# novelkey_esp.net
KiCad netlist of a schematic drawn in EAGLE
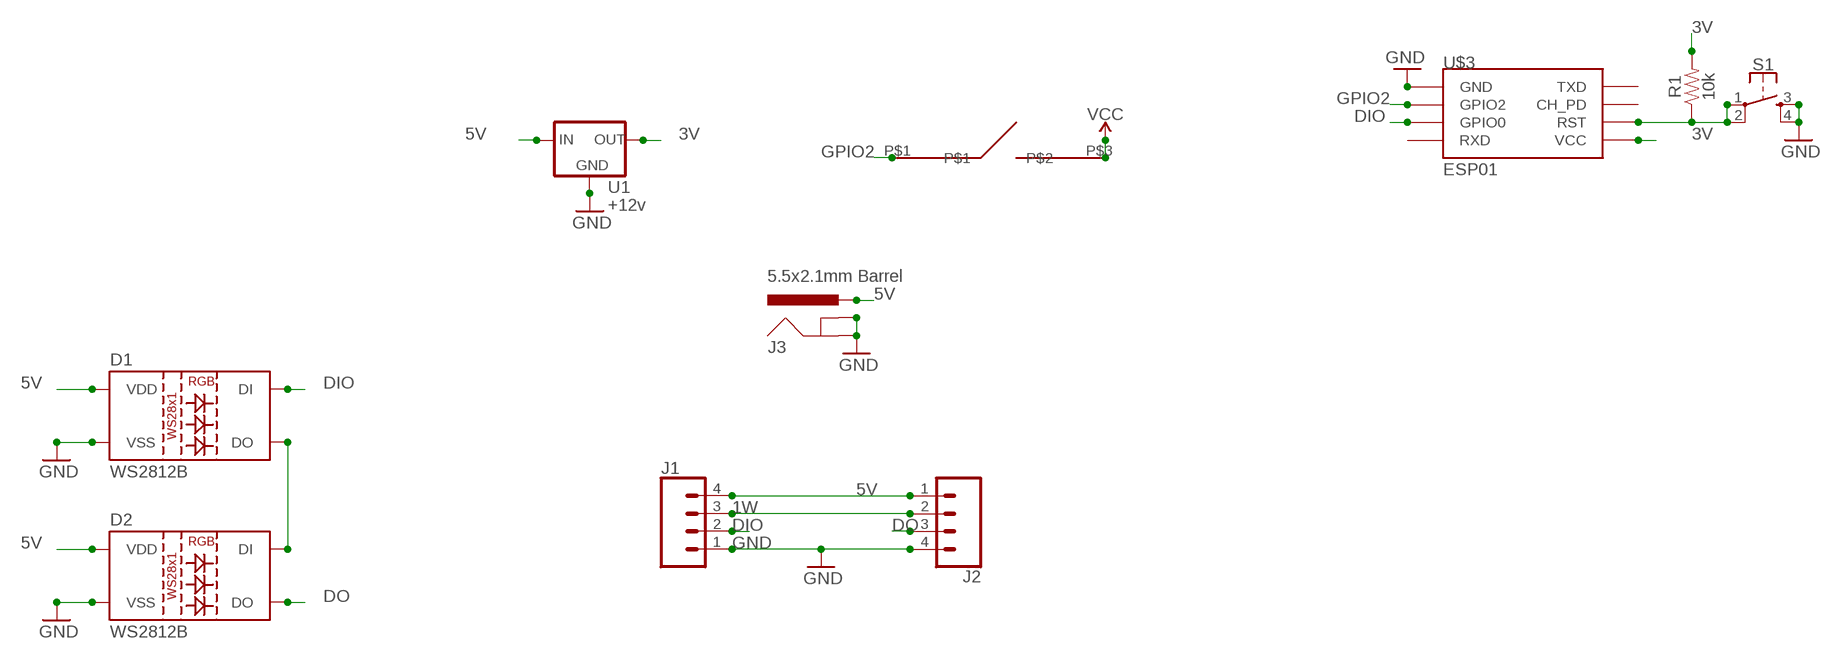
[diagram p0: schematic, sheet 1]

(export (version "E")
  (design (tool "Eeschema 10.0.6"))
  (components
    (comp (ref "D1")
      (value "WS2812B")
      (footprint "eagle-import:WS2812B")
      (libsource (lib "eagle-import") (part "WS2812B"))
    )
    (comp (ref "D2")
      (value "WS2812B")
      (footprint "eagle-import:WS2812B")
      (libsource (lib "eagle-import") (part "WS2812B"))
    )
    (comp (ref "J1")
      (value "CONN_04SMD2")
      (footprint "eagle-import:1X04_1MM_RA")
      (libsource (lib "eagle-import") (part "CONN_04SMD2"))
    )
    (comp (ref "J2")
      (value "CONN_04SMD2")
      (footprint "eagle-import:1X04_1MM_RA")
      (libsource (lib "eagle-import") (part "CONN_04SMD2"))
    )
    (comp (ref "J3")
      (value "5.5x2.1mm Barrel")
      (footprint "eagle-import:POWER_JACK_SMD")
      (libsource (lib "eagle-import") (part "POWER_JACKSMD"))
    )
    (comp (ref "R1")
      (value "10k")
      (footprint "eagle-import:0603")
      (libsource (lib "eagle-import") (part "10KOHM-0603-1/10W-1%"))
    )
    (comp (ref "S1")
      (value "MOMENTARY-SWITCH-SPST-2-SMD-4.6X2.8MM")
      (footprint "eagle-import:TACTILE_SWITCH_SMD_4.6X2.8MM")
      (libsource (lib "eagle-import") (part "MOMENTARY-SWITCH-SPST-2-SMD-4.6X2.8MM"))
    )
    (comp (ref "U$1")
      (value "NOVELKEY")
      (footprint "eagle-import:NOVELKEY")
      (libsource (lib "eagle-import") (part "NOVELKEY"))
    )
    (comp (ref "U$3")
      (value "ESP01")
      (footprint "eagle-import:ESP01")
      (libsource (lib "eagle-import") (part "ESP01"))
    )
    (comp (ref "U1")
      (value "+12v")
      (footprint "eagle-import:TO-252")
      (libsource (lib "eagle-import") (part "V_REG_78XX7812"))
    )
  )
  (nets
    (net (code "1") (name "/1W") (class "Default")
      (node (ref "J1") (pin "3") (pinfunction "3_3") (pintype "passive"))
      (node (ref "J2") (pin "2") (pinfunction "2_2") (pintype "passive"))
    )
    (net (code "2") (name "/3V") (class "Default")
      (node (ref "R1") (pin "2") (pinfunction "2_2") (pintype "passive"))
      (node (ref "U$3") (pin "VCC") (pinfunction "VCC_VCC") (pintype "bidirectional"))
      (node (ref "U1") (pin "2") (pinfunction "OUT_2") (pintype "passive"))
    )
    (net (code "3") (name "/5V") (class "Default")
      (node (ref "D1") (pin "1") (pinfunction "VDD_1") (pintype "bidirectional"))
      (node (ref "D2") (pin "1") (pinfunction "VDD_1") (pintype "bidirectional"))
      (node (ref "J1") (pin "4") (pinfunction "4_4") (pintype "passive"))
      (node (ref "J2") (pin "1") (pinfunction "1_1") (pintype "passive"))
      (node (ref "J3") (pin "VIN0") (pinfunction "PWR_VIN0") (pintype "bidirectional"))
      (node (ref "U1") (pin "1") (pinfunction "IN_1") (pintype "input"))
    )
    (net (code "4") (name "/DIO") (class "Default")
      (node (ref "D1") (pin "4") (pinfunction "DI_4") (pintype "bidirectional"))
      (node (ref "J1") (pin "2") (pinfunction "2_2") (pintype "passive"))
      (node (ref "U$3") (pin "GPIO0") (pinfunction "GPIO0_GPIO0") (pintype "bidirectional"))
    )
    (net (code "5") (name "/DO") (class "Default")
      (node (ref "D2") (pin "2") (pinfunction "DO_2") (pintype "bidirectional"))
      (node (ref "J2") (pin "3") (pinfunction "3_3") (pintype "passive"))
    )
    (net (code "6") (name "/GPIO2") (class "Default")
      (node (ref "U$1") (pin "P$1") (pinfunction "P$1_P$1") (pintype "bidirectional"))
      (node (ref "U$3") (pin "GPIO2") (pinfunction "GPIO2_GPIO2") (pintype "bidirectional"))
    )
    (net (code "7") (name "GND") (class "Default")
      (node (ref "D1") (pin "3") (pinfunction "VSS_3") (pintype "bidirectional"))
      (node (ref "D2") (pin "3") (pinfunction "VSS_3") (pintype "bidirectional"))
      (node (ref "J1") (pin "1") (pinfunction "1_1") (pintype "passive"))
      (node (ref "J2") (pin "4") (pinfunction "4_4") (pintype "passive"))
      (node (ref "J3") (pin "GND") (pinfunction "GNDBREAK_GND") (pintype "bidirectional"))
      (node (ref "J3") (pin "P$4") (pinfunction "GND_P$4") (pintype "bidirectional"))
      (node (ref "S1") (pin "3") (pinfunction "3_3") (pintype "passive"))
      (node (ref "S1") (pin "4") (pinfunction "4_4") (pintype "passive"))
      (node (ref "U$3") (pin "GND") (pinfunction "GND_GND") (pintype "bidirectional"))
      (node (ref "U1") (pin "3") (pinfunction "GND_3") (pintype "input"))
    )
    (net (code "8") (name "Net-(D1-DO)") (class "Default")
      (node (ref "D1") (pin "2") (pinfunction "DO_2") (pintype "bidirectional"))
      (node (ref "D2") (pin "4") (pinfunction "DI_4") (pintype "bidirectional"))
    )
    (net (code "9") (name "Net-(R1-Pad1)") (class "Default")
      (node (ref "R1") (pin "1") (pinfunction "1_1") (pintype "passive"))
      (node (ref "S1") (pin "1") (pinfunction "1_1") (pintype "passive"))
      (node (ref "S1") (pin "2") (pinfunction "2_2") (pintype "passive"))
      (node (ref "U$3") (pin "RST") (pinfunction "RST_RST") (pintype "bidirectional"))
    )
    (net (code "10") (name "VCC") (class "Default")
      (node (ref "U$1") (pin "P$3") (pinfunction "P$2_P$3") (pintype "bidirectional"))
    )
    (net (code "11") (name "unconnected-(U$3-PadCH_PD)") (class "Default")
      (node (ref "U$3") (pin "CH_PD") (pinfunction "CH_PD_CH_PD") (pintype "bidirectional"))
    )
    (net (code "12") (name "unconnected-(U$3-RXD-PadRX)") (class "Default")
      (node (ref "U$3") (pin "RX") (pinfunction "RXD_RX") (pintype "bidirectional"))
    )
    (net (code "13") (name "unconnected-(U$3-TXD-PadTX)") (class "Default")
      (node (ref "U$3") (pin "TX") (pinfunction "TXD_TX") (pintype "bidirectional"))
    )
  )
)
